# loochi-0_6.net
KiCad netlist of a schematic drawn in EAGLE
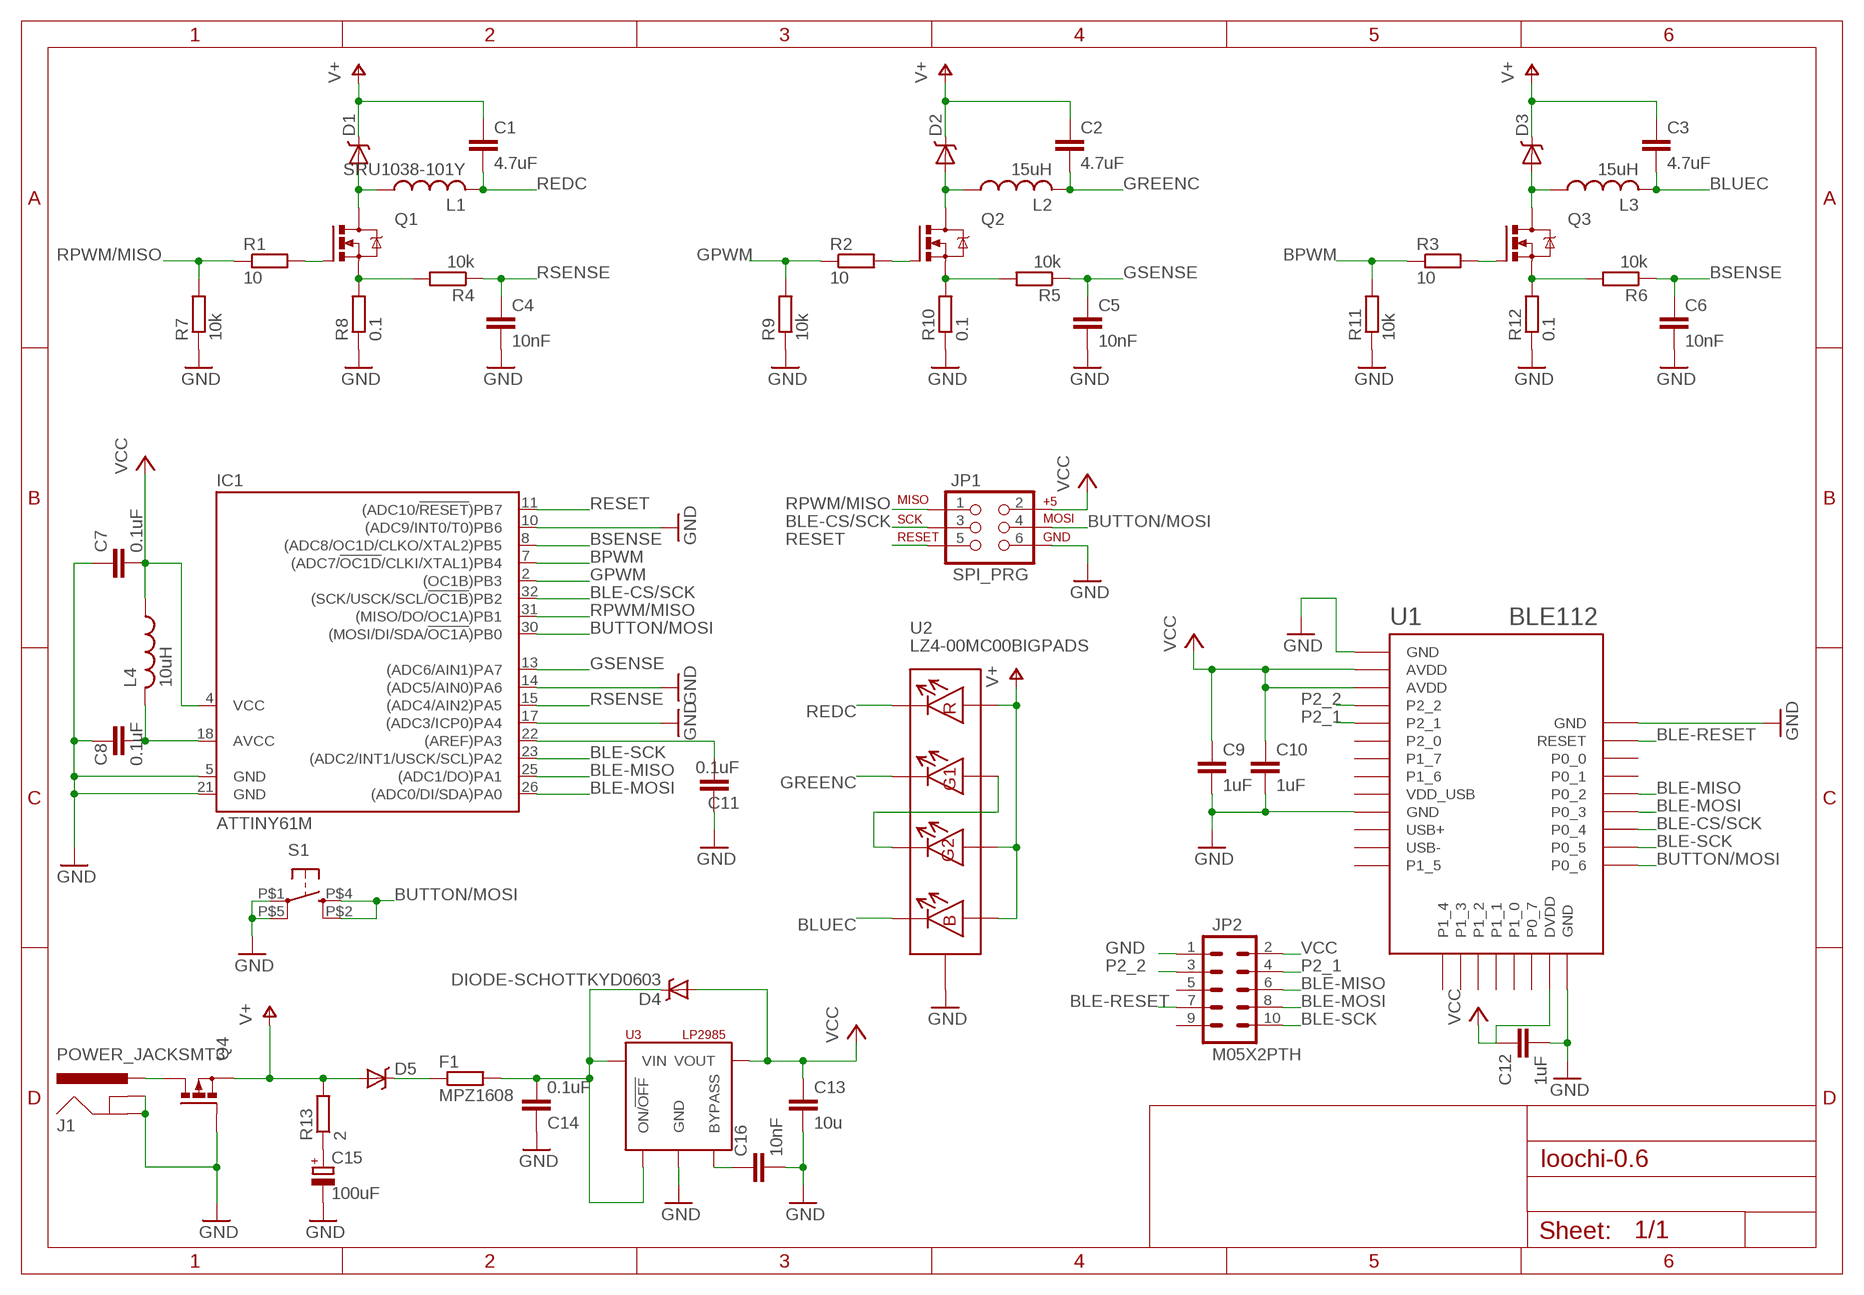
[diagram p0: schematic, sheet 1]

(export (version "E")
  (design (tool "Eeschema 10.0.6"))
  (components
    (comp (ref "C1")
      (value "4.7uF")
      (footprint "eagle-import:C0603")
      (libsource (lib "eagle-import") (part "C-EUC0603"))
    )
    (comp (ref "C2")
      (value "4.7uF")
      (footprint "eagle-import:C0603")
      (libsource (lib "eagle-import") (part "C-EUC0603"))
    )
    (comp (ref "C3")
      (value "4.7uF")
      (footprint "eagle-import:C0603")
      (libsource (lib "eagle-import") (part "C-EUC0603"))
    )
    (comp (ref "C4")
      (value "10nF")
      (footprint "eagle-import:C0603")
      (libsource (lib "eagle-import") (part "C-EUC0603"))
    )
    (comp (ref "C5")
      (value "10nF")
      (footprint "eagle-import:C0603")
      (libsource (lib "eagle-import") (part "C-EUC0603"))
    )
    (comp (ref "C6")
      (value "10nF")
      (footprint "eagle-import:C0603")
      (libsource (lib "eagle-import") (part "C-EUC0603"))
    )
    (comp (ref "C7")
      (value "0.1uF")
      (footprint "eagle-import:C0603")
      (libsource (lib "eagle-import") (part "C-EUC0603"))
    )
    (comp (ref "C8")
      (value "0.1uF")
      (footprint "eagle-import:C0603")
      (libsource (lib "eagle-import") (part "C-EUC0603"))
    )
    (comp (ref "C9")
      (value "1uF")
      (footprint "eagle-import:C0603")
      (libsource (lib "eagle-import") (part "C-EUC0603"))
    )
    (comp (ref "C10")
      (value "1uF")
      (footprint "eagle-import:C0603")
      (libsource (lib "eagle-import") (part "C-EUC0603"))
    )
    (comp (ref "C11")
      (value "0.1uF")
      (footprint "eagle-import:C0603")
      (libsource (lib "eagle-import") (part "C-EUC0603"))
    )
    (comp (ref "C12")
      (value "1uF")
      (footprint "eagle-import:C0603")
      (libsource (lib "eagle-import") (part "C-EUC0603"))
    )
    (comp (ref "C13")
      (value "10u")
      (footprint "eagle-import:C0603")
      (libsource (lib "eagle-import") (part "C-EUC0603"))
    )
    (comp (ref "C14")
      (value "0.1uF")
      (footprint "eagle-import:C0603K")
      (libsource (lib "eagle-import") (part "C-EUC0603K"))
    )
    (comp (ref "C15")
      (value "100uF")
      (footprint "eagle-import:PANASONIC_D")
      (libsource (lib "eagle-import") (part "CPOL-EUD"))
    )
    (comp (ref "C16")
      (value "10nF")
      (footprint "eagle-import:C0603")
      (libsource (lib "eagle-import") (part "C-EUC0603"))
    )
    (comp (ref "D1")
      (value "PMEG4010CEH")
      (footprint "eagle-import:SOD123F")
      (libsource (lib "eagle-import") (part "DIODE-SCHOTTKY"))
    )
    (comp (ref "D2")
      (value "PMEG4010CEH")
      (footprint "eagle-import:SOD123F")
      (libsource (lib "eagle-import") (part "DIODE-SCHOTTKY"))
    )
    (comp (ref "D3")
      (value "PMEG4010CEH")
      (footprint "eagle-import:SOD123F")
      (libsource (lib "eagle-import") (part "DIODE-SCHOTTKY"))
    )
    (comp (ref "D4")
      (value "DIODE-SCHOTTKYD0603")
      (footprint "eagle-import:D0603")
      (libsource (lib "eagle-import") (part "DIODE-SCHOTTKYD0603"))
    )
    (comp (ref "D5")
      (value "PMEG4010CEH")
      (footprint "eagle-import:SOD123F")
      (libsource (lib "eagle-import") (part "DIODE-SCHOTTKY"))
    )
    (comp (ref "F1")
      (value "MPZ1608")
      (footprint "eagle-import:R0603")
      (libsource (lib "eagle-import") (part "R-EU_R0603"))
    )
    (comp (ref "IC1")
      (value "ATTINY61M")
      (footprint "eagle-import:MLF32")
      (fields (field (name "OC_FARNELL") "unknown") (field (name "OC_NEWARK") "unknown"))
      (libsource (lib "eagle-import") (part "ATTINY61M"))
    )
    (comp (ref "J1")
      (value "POWER_JACKSMT3")
      (footprint "eagle-import:POWER-KYCONSMT3")
      (libsource (lib "eagle-import") (part "POWER_JACKSMT3"))
    )
    (comp (ref "JP1")
      (value "SPI_PRG")
      (footprint "eagle-import:2X3-NS")
      (libsource (lib "eagle-import") (part "AVR_SPI_PRG_6NS"))
    )
    (comp (ref "JP2")
      (value "M05X2PTH")
      (footprint "eagle-import:AVR_ICSP")
      (libsource (lib "eagle-import") (part "M05X2PTH"))
    )
    (comp (ref "L1")
      (value "SRU1038-101Y")
      (footprint "eagle-import:BOURNS-SRU1038")
      (libsource (lib "eagle-import") (part "L-USBOURNS-SRU1038"))
    )
    (comp (ref "L2")
      (value "15uH")
      (footprint "eagle-import:BOURNS-SRU1038")
      (libsource (lib "eagle-import") (part "L-USBOURNS-SRU1038"))
    )
    (comp (ref "L3")
      (value "15uH")
      (footprint "eagle-import:BOURNS-SRU1038")
      (libsource (lib "eagle-import") (part "L-USBOURNS-SRU1038"))
    )
    (comp (ref "L4")
      (value "10uH")
      (footprint "eagle-import:L0603")
      (libsource (lib "eagle-import") (part "L-USL0603"))
    )
    (comp (ref "Q1")
      (value "PMN25ENSOT457")
      (footprint "eagle-import:SOT457")
      (libsource (lib "eagle-import") (part "PMN25ENSOT457"))
    )
    (comp (ref "Q2")
      (value "PMN25ENSOT457")
      (footprint "eagle-import:SOT457")
      (libsource (lib "eagle-import") (part "PMN25ENSOT457"))
    )
    (comp (ref "Q3")
      (value "PMN25ENSOT457")
      (footprint "eagle-import:SOT457")
      (libsource (lib "eagle-import") (part "PMN25ENSOT457"))
    )
    (comp (ref "Q4")
      (value "FDC654P")
      (footprint "eagle-import:SUPERSOT6")
      (libsource (lib "eagle-import") (part "FDC654P"))
    )
    (comp (ref "R1")
      (value "10")
      (footprint "eagle-import:R0603")
      (libsource (lib "eagle-import") (part "R-EU_R0603"))
    )
    (comp (ref "R2")
      (value "10")
      (footprint "eagle-import:R0603")
      (libsource (lib "eagle-import") (part "R-EU_R0603"))
    )
    (comp (ref "R3")
      (value "10")
      (footprint "eagle-import:R0603")
      (libsource (lib "eagle-import") (part "R-EU_R0603"))
    )
    (comp (ref "R4")
      (value "10k")
      (footprint "eagle-import:R0603")
      (libsource (lib "eagle-import") (part "R-EU_R0603"))
    )
    (comp (ref "R5")
      (value "10k")
      (footprint "eagle-import:R0603")
      (libsource (lib "eagle-import") (part "R-EU_R0603"))
    )
    (comp (ref "R6")
      (value "10k")
      (footprint "eagle-import:R0603")
      (libsource (lib "eagle-import") (part "R-EU_R0603"))
    )
    (comp (ref "R7")
      (value "10k")
      (footprint "eagle-import:R0603")
      (libsource (lib "eagle-import") (part "R-EU_R0603"))
    )
    (comp (ref "R8")
      (value "0.1")
      (footprint "eagle-import:R0603")
      (libsource (lib "eagle-import") (part "R-EU_R0603"))
    )
    (comp (ref "R9")
      (value "10k")
      (footprint "eagle-import:R0603")
      (libsource (lib "eagle-import") (part "R-EU_R0603"))
    )
    (comp (ref "R10")
      (value "0.1")
      (footprint "eagle-import:R0603")
      (libsource (lib "eagle-import") (part "R-EU_R0603"))
    )
    (comp (ref "R11")
      (value "10k")
      (footprint "eagle-import:R0603")
      (libsource (lib "eagle-import") (part "R-EU_R0603"))
    )
    (comp (ref "R12")
      (value "0.1")
      (footprint "eagle-import:R0603")
      (libsource (lib "eagle-import") (part "R-EU_R0603"))
    )
    (comp (ref "R13")
      (value "2")
      (footprint "eagle-import:R0603")
      (libsource (lib "eagle-import") (part "R-EU_R0603"))
    )
    (comp (ref "S1")
      (value "TAC_SWITCH")
      (footprint "eagle-import:CK-KMS_PEGS")
      (libsource (lib "eagle-import") (part "TAC_SWITCH"))
    )
    (comp (ref "U1")
      (value "BLE112")
      (footprint "eagle-import:SF-BLUEGIGA_BLE112-A")
      (libsource (lib "eagle-import") (part "SF-BLUEGIGA_BLE112-A-VISUAL"))
    )
    (comp (ref "U2")
      (value "LZ4-00MC00BIGPADS")
      (footprint "eagle-import:LZ4-00MC00-BIGPADS")
      (libsource (lib "eagle-import") (part "LZ4-00MC00BIGPADS"))
    )
    (comp (ref "U3")
      (value "LP2985")
      (footprint "eagle-import:DBV")
      (libsource (lib "eagle-import") (part "LP2985"))
    )
  )
  (nets
    (net (code "1") (name "/BLE-CS{slash}SCK") (class "Default")
      (node (ref "IC1") (pin "32") (pinfunction "(SCK/USCK/SCL/~{OC1B})PB2_32") (pintype "bidirectional"))
      (node (ref "JP1") (pin "3") (pinfunction "3_3") (pintype "passive"))
      (node (ref "U1") (pin "P0_4") (pinfunction "P0_4_P0_4") (pintype "bidirectional"))
    )
    (net (code "2") (name "/BLE-MISO") (class "Default")
      (node (ref "IC1") (pin "25") (pinfunction "(ADC1/DO)PA1_25") (pintype "bidirectional"))
      (node (ref "JP2") (pin "6") (pinfunction "6_6") (pintype "passive"))
      (node (ref "U1") (pin "P0_2") (pinfunction "P0_2_P0_2") (pintype "bidirectional"))
    )
    (net (code "3") (name "/BLE-MOSI") (class "Default")
      (node (ref "IC1") (pin "26") (pinfunction "(ADC0/DI/SDA)PA0_26") (pintype "bidirectional"))
      (node (ref "JP2") (pin "8") (pinfunction "8_8") (pintype "passive"))
      (node (ref "U1") (pin "P0_3") (pinfunction "P0_3_P0_3") (pintype "bidirectional"))
    )
    (net (code "4") (name "/BLE-RESET") (class "Default")
      (node (ref "JP2") (pin "7") (pinfunction "7_7") (pintype "passive"))
      (node (ref "U1") (pin "RESET") (pinfunction "RESET_RESET") (pintype "input"))
    )
    (net (code "5") (name "/BLE-SCK") (class "Default")
      (node (ref "IC1") (pin "23") (pinfunction "(ADC2/INT1/USCK/SCL)PA2_23") (pintype "bidirectional"))
      (node (ref "JP2") (pin "10") (pinfunction "10_10") (pintype "passive"))
      (node (ref "U1") (pin "P0_5") (pinfunction "P0_5_P0_5") (pintype "bidirectional"))
    )
    (net (code "6") (name "/BLUEC") (class "Default")
      (node (ref "C3") (pin "2") (pinfunction "2_2") (pintype "passive"))
      (node (ref "L3") (pin "P$2") (pinfunction "2_P$2") (pintype "passive"))
      (node (ref "U2") (pin "P$8") (pinfunction "P$8_P$8") (pintype "bidirectional"))
    )
    (net (code "7") (name "/BPWM") (class "Default")
      (node (ref "IC1") (pin "7") (pinfunction "(ADC7/~{OC1D}/CLKI/XTAL1)PB4_7") (pintype "bidirectional"))
      (node (ref "R11") (pin "2") (pinfunction "2_2") (pintype "passive"))
      (node (ref "R3") (pin "1") (pinfunction "1_1") (pintype "passive"))
    )
    (net (code "8") (name "/BSENSE") (class "Default")
      (node (ref "C6") (pin "1") (pinfunction "1_1") (pintype "passive"))
      (node (ref "IC1") (pin "8") (pinfunction "(ADC8/OC1D/CLKO/XTAL2)PB5_8") (pintype "bidirectional"))
      (node (ref "R6") (pin "1") (pinfunction "1_1") (pintype "passive"))
    )
    (net (code "9") (name "/BUTTON{slash}MOSI") (class "Default")
      (node (ref "IC1") (pin "30") (pinfunction "(MOSI/DI/SDA/~{OC1A})PB0_30") (pintype "bidirectional"))
      (node (ref "JP1") (pin "4") (pinfunction "4_4") (pintype "passive"))
      (node (ref "S1") (pin "P$2") (pinfunction "4_P$2") (pintype "passive"))
      (node (ref "S1") (pin "P$4") (pinfunction "3_P$4") (pintype "passive"))
      (node (ref "U1") (pin "P0_6") (pinfunction "P0_6_P0_6") (pintype "bidirectional"))
    )
    (net (code "10") (name "/GPWM") (class "Default")
      (node (ref "IC1") (pin "2") (pinfunction "(OC1B)PB3_2") (pintype "bidirectional"))
      (node (ref "R2") (pin "1") (pinfunction "1_1") (pintype "passive"))
      (node (ref "R9") (pin "2") (pinfunction "2_2") (pintype "passive"))
    )
    (net (code "11") (name "/GREENC") (class "Default")
      (node (ref "C2") (pin "2") (pinfunction "2_2") (pintype "passive"))
      (node (ref "L2") (pin "P$2") (pinfunction "2_P$2") (pintype "passive"))
      (node (ref "U2") (pin "P$6") (pinfunction "P$6_P$6") (pintype "bidirectional"))
    )
    (net (code "12") (name "/GSENSE") (class "Default")
      (node (ref "C5") (pin "1") (pinfunction "1_1") (pintype "passive"))
      (node (ref "IC1") (pin "13") (pinfunction "(ADC6/AIN1)PA7_13") (pintype "bidirectional"))
      (node (ref "R5") (pin "1") (pinfunction "1_1") (pintype "passive"))
    )
    (net (code "13") (name "/P2_1") (class "Default")
      (node (ref "JP2") (pin "4") (pinfunction "4_4") (pintype "passive"))
      (node (ref "U1") (pin "P2_1") (pinfunction "P2_1_P2_1") (pintype "bidirectional"))
    )
    (net (code "14") (name "/P2_2") (class "Default")
      (node (ref "JP2") (pin "3") (pinfunction "3_3") (pintype "passive"))
      (node (ref "U1") (pin "P2_2") (pinfunction "P2_2_P2_2") (pintype "bidirectional"))
    )
    (net (code "15") (name "/REDC") (class "Default")
      (node (ref "C1") (pin "2") (pinfunction "2_2") (pintype "passive"))
      (node (ref "L1") (pin "P$2") (pinfunction "2_P$2") (pintype "passive"))
      (node (ref "U2") (pin "P$4") (pinfunction "P$4_P$4") (pintype "bidirectional"))
    )
    (net (code "16") (name "/RESET") (class "Default")
      (node (ref "IC1") (pin "11") (pinfunction "(ADC10/~{RESET})PB7_11") (pintype "bidirectional"))
      (node (ref "JP1") (pin "5") (pinfunction "5_5") (pintype "passive"))
    )
    (net (code "17") (name "/RPWM{slash}MISO") (class "Default")
      (node (ref "IC1") (pin "31") (pinfunction "(MISO/DO/OC1A)PB1_31") (pintype "bidirectional"))
      (node (ref "JP1") (pin "1") (pinfunction "1_1") (pintype "passive"))
      (node (ref "R1") (pin "1") (pinfunction "1_1") (pintype "passive"))
      (node (ref "R7") (pin "2") (pinfunction "2_2") (pintype "passive"))
    )
    (net (code "18") (name "/RSENSE") (class "Default")
      (node (ref "C4") (pin "1") (pinfunction "1_1") (pintype "passive"))
      (node (ref "IC1") (pin "15") (pinfunction "(ADC4/AIN2)PA5_15") (pintype "bidirectional"))
      (node (ref "R4") (pin "1") (pinfunction "1_1") (pintype "passive"))
    )
    (net (code "19") (name "/VDD_USB") (class "Default")
      (node (ref "U1") (pin "VDD_USB") (pinfunction "VDD_USB_VDD_USB") (pintype "power_in"))
    )
    (net (code "20") (name "GND") (class "Default")
      (node (ref "C10") (pin "2") (pinfunction "2_2") (pintype "passive"))
      (node (ref "C11") (pin "1") (pinfunction "1_1") (pintype "passive"))
      (node (ref "C12") (pin "2") (pinfunction "2_2") (pintype "passive"))
      (node (ref "C13") (pin "2") (pinfunction "2_2") (pintype "passive"))
      (node (ref "C14") (pin "1") (pinfunction "1_1") (pintype "passive"))
      (node (ref "C15") (pin "-") (pinfunction "-_-") (pintype "passive"))
      (node (ref "C16") (pin "2") (pinfunction "2_2") (pintype "passive"))
      (node (ref "C4") (pin "2") (pinfunction "2_2") (pintype "passive"))
      (node (ref "C5") (pin "2") (pinfunction "2_2") (pintype "passive"))
      (node (ref "C6") (pin "2") (pinfunction "2_2") (pintype "passive"))
      (node (ref "C7") (pin "1") (pinfunction "1_1") (pintype "passive"))
      (node (ref "C8") (pin "1") (pinfunction "1_1") (pintype "passive"))
      (node (ref "C9") (pin "2") (pinfunction "2_2") (pintype "passive"))
      (node (ref "IC1") (pin "10") (pinfunction "(ADC9/INT0/T0)PB6_10") (pintype "bidirectional"))
      (node (ref "IC1") (pin "14") (pinfunction "(ADC5/AIN0)PA6_14") (pintype "bidirectional"))
      (node (ref "IC1") (pin "17") (pinfunction "(ADC3/ICP0)PA4_17") (pintype "bidirectional"))
      (node (ref "IC1") (pin "21") (pinfunction "GND_21") (pintype "power_in"))
      (node (ref "IC1") (pin "5") (pinfunction "GND_5") (pintype "power_in"))
      (node (ref "J1") (pin "P$2") (pinfunction "GND_P$2") (pintype "bidirectional"))
      (node (ref "J1") (pin "P$3") (pinfunction "GNDBREAK_P$3") (pintype "bidirectional"))
      (node (ref "JP1") (pin "6") (pinfunction "6_6") (pintype "passive"))
      (node (ref "JP2") (pin "1") (pinfunction "1_1") (pintype "passive"))
      (node (ref "Q4") (pin "P$3") (pinfunction "G_P$3") (pintype "passive"))
      (node (ref "R10") (pin "1") (pinfunction "1_1") (pintype "passive"))
      (node (ref "R11") (pin "1") (pinfunction "1_1") (pintype "passive"))
      (node (ref "R12") (pin "1") (pinfunction "1_1") (pintype "passive"))
      (node (ref "R7") (pin "1") (pinfunction "1_1") (pintype "passive"))
      (node (ref "R8") (pin "1") (pinfunction "1_1") (pintype "passive"))
      (node (ref "R9") (pin "1") (pinfunction "1_1") (pintype "passive"))
      (node (ref "S1") (pin "P$1") (pinfunction "1_P$1") (pintype "passive"))
      (node (ref "S1") (pin "P$5") (pinfunction "2_P$5") (pintype "passive"))
      (node (ref "U1") (pin "GND1") (pinfunction "GND_GND1") (pintype "power_in"))
      (node (ref "U1") (pin "GND2") (pinfunction "GND_GND2") (pintype "power_in"))
      (node (ref "U1") (pin "GND3") (pinfunction "GND_GND3") (pintype "power_in"))
      (node (ref "U1") (pin "GND4") (pinfunction "GND_GND4") (pintype "power_in"))
      (node (ref "U2") (pin "P$9") (pinfunction "THERMAL_P$9") (pintype "bidirectional"))
      (node (ref "U2") (pin "THERMAL") (pinfunction "THERMAL_THERMAL") (pintype "bidirectional"))
      (node (ref "U2") (pin "THERMAL1") (pinfunction "THERMAL_THERMAL1") (pintype "bidirectional"))
      (node (ref "U2") (pin "THERMAL2") (pinfunction "THERMAL_THERMAL2") (pintype "bidirectional"))
      (node (ref "U2") (pin "THERMAL3") (pinfunction "THERMAL_THERMAL3") (pintype "bidirectional"))
      (node (ref "U2") (pin "THERMAL4") (pinfunction "THERMAL_THERMAL4") (pintype "bidirectional"))
      (node (ref "U2") (pin "THERMAL5") (pinfunction "THERMAL_THERMAL5") (pintype "bidirectional"))
      (node (ref "U2") (pin "THERMAL6") (pinfunction "THERMAL_THERMAL6") (pintype "bidirectional"))
      (node (ref "U2") (pin "THERMAL7") (pinfunction "THERMAL_THERMAL7") (pintype "bidirectional"))
      (node (ref "U2") (pin "THERMAL8") (pinfunction "THERMAL_THERMAL8") (pintype "bidirectional"))
      (node (ref "U2") (pin "THERMAL9") (pinfunction "THERMAL_THERMAL9") (pintype "bidirectional"))
      (node (ref "U3") (pin "2") (pinfunction "GND_2") (pintype "power_in"))
    )
    (net (code "21") (name "Net-(C15-Pad+)") (class "Default")
      (node (ref "C15") (pin "+") (pinfunction "+_+") (pintype "passive"))
      (node (ref "R13") (pin "1") (pinfunction "1_1") (pintype "passive"))
    )
    (net (code "22") (name "Net-(D1-A)") (class "Default")
      (node (ref "D1") (pin "P$A") (pinfunction "A_P$A") (pintype "passive"))
      (node (ref "L1") (pin "P$1") (pinfunction "1_P$1") (pintype "passive"))
      (node (ref "Q1") (pin "P$1") (pinfunction "D_P$1") (pintype "passive"))
      (node (ref "Q1") (pin "P$2") (pinfunction "D_P$2") (pintype "passive"))
      (node (ref "Q1") (pin "P$5") (pinfunction "D_P$5") (pintype "passive"))
      (node (ref "Q1") (pin "P$6") (pinfunction "D_P$6") (pintype "passive"))
    )
    (net (code "23") (name "Net-(D2-A)") (class "Default")
      (node (ref "D2") (pin "P$A") (pinfunction "A_P$A") (pintype "passive"))
      (node (ref "L2") (pin "P$1") (pinfunction "1_P$1") (pintype "passive"))
      (node (ref "Q2") (pin "P$1") (pinfunction "D_P$1") (pintype "passive"))
      (node (ref "Q2") (pin "P$2") (pinfunction "D_P$2") (pintype "passive"))
      (node (ref "Q2") (pin "P$5") (pinfunction "D_P$5") (pintype "passive"))
      (node (ref "Q2") (pin "P$6") (pinfunction "D_P$6") (pintype "passive"))
    )
    (net (code "24") (name "Net-(D3-A)") (class "Default")
      (node (ref "D3") (pin "P$A") (pinfunction "A_P$A") (pintype "passive"))
      (node (ref "L3") (pin "P$1") (pinfunction "1_P$1") (pintype "passive"))
      (node (ref "Q3") (pin "P$1") (pinfunction "D_P$1") (pintype "passive"))
      (node (ref "Q3") (pin "P$2") (pinfunction "D_P$2") (pintype "passive"))
      (node (ref "Q3") (pin "P$5") (pinfunction "D_P$5") (pintype "passive"))
      (node (ref "Q3") (pin "P$6") (pinfunction "D_P$6") (pintype "passive"))
    )
    (net (code "25") (name "Net-(D4-C)") (class "Default")
      (node (ref "C14") (pin "2") (pinfunction "2_2") (pintype "passive"))
      (node (ref "D4") (pin "CATHODE") (pinfunction "C_CATHODE") (pintype "passive"))
      (node (ref "F1") (pin "2") (pinfunction "2_2") (pintype "passive"))
      (node (ref "U3") (pin "1") (pinfunction "VIN_1") (pintype "power_in"))
      (node (ref "U3") (pin "3") (pinfunction "ON/~{OFF}_3") (pintype "bidirectional"))
    )
    (net (code "26") (name "Net-(D5-C)") (class "Default")
      (node (ref "D5") (pin "P$C") (pinfunction "C_P$C") (pintype "passive"))
      (node (ref "F1") (pin "1") (pinfunction "1_1") (pintype "passive"))
    )
    (net (code "27") (name "Net-(IC1-(AREF)PA3)") (class "Default")
      (node (ref "C11") (pin "2") (pinfunction "2_2") (pintype "passive"))
      (node (ref "IC1") (pin "22") (pinfunction "(AREF)PA3_22") (pintype "bidirectional"))
    )
    (net (code "28") (name "Net-(IC1-AVCC)") (class "Default")
      (node (ref "C8") (pin "2") (pinfunction "2_2") (pintype "passive"))
      (node (ref "IC1") (pin "18") (pinfunction "AVCC_18") (pintype "power_in"))
      (node (ref "L4") (pin "2") (pinfunction "2_2") (pintype "passive"))
    )
    (net (code "29") (name "Net-(J1-PWR)") (class "Default")
      (node (ref "J1") (pin "P$1") (pinfunction "PWR_P$1") (pintype "bidirectional"))
      (node (ref "Q4") (pin "P$1") (pinfunction "D_P$1") (pintype "passive"))
      (node (ref "Q4") (pin "P$2") (pinfunction "D_P$2") (pintype "passive"))
      (node (ref "Q4") (pin "P$5") (pinfunction "D_P$5") (pintype "passive"))
      (node (ref "Q4") (pin "P$6") (pinfunction "D_P$6") (pintype "passive"))
    )
    (net (code "30") (name "Net-(Q1-G)") (class "Default")
      (node (ref "Q1") (pin "P$3") (pinfunction "G_P$3") (pintype "passive"))
      (node (ref "R1") (pin "2") (pinfunction "2_2") (pintype "passive"))
    )
    (net (code "31") (name "Net-(Q1-S)") (class "Default")
      (node (ref "Q1") (pin "P$4") (pinfunction "S_P$4") (pintype "passive"))
      (node (ref "R4") (pin "2") (pinfunction "2_2") (pintype "passive"))
      (node (ref "R8") (pin "2") (pinfunction "2_2") (pintype "passive"))
    )
    (net (code "32") (name "Net-(Q2-G)") (class "Default")
      (node (ref "Q2") (pin "P$3") (pinfunction "G_P$3") (pintype "passive"))
      (node (ref "R2") (pin "2") (pinfunction "2_2") (pintype "passive"))
    )
    (net (code "33") (name "Net-(Q2-S)") (class "Default")
      (node (ref "Q2") (pin "P$4") (pinfunction "S_P$4") (pintype "passive"))
      (node (ref "R10") (pin "2") (pinfunction "2_2") (pintype "passive"))
      (node (ref "R5") (pin "2") (pinfunction "2_2") (pintype "passive"))
    )
    (net (code "34") (name "Net-(Q3-G)") (class "Default")
      (node (ref "Q3") (pin "P$3") (pinfunction "G_P$3") (pintype "passive"))
      (node (ref "R3") (pin "2") (pinfunction "2_2") (pintype "passive"))
    )
    (net (code "35") (name "Net-(Q3-S)") (class "Default")
      (node (ref "Q3") (pin "P$4") (pinfunction "S_P$4") (pintype "passive"))
      (node (ref "R12") (pin "2") (pinfunction "2_2") (pintype "passive"))
      (node (ref "R6") (pin "2") (pinfunction "2_2") (pintype "passive"))
    )
    (net (code "36") (name "Net-(U2-PadP$2)") (class "Default")
      (node (ref "U2") (pin "P$2") (pinfunction "P$2_P$2") (pintype "bidirectional"))
      (node (ref "U2") (pin "P$5") (pinfunction "P$5_P$5") (pintype "bidirectional"))
    )
    (net (code "37") (name "Net-(U3-BYPASS)") (class "Default")
      (node (ref "C16") (pin "1") (pinfunction "1_1") (pintype "passive"))
      (node (ref "U3") (pin "4") (pinfunction "BYPASS_4") (pintype "bidirectional"))
    )
    (net (code "38") (name "V+") (class "Default")
      (node (ref "C1") (pin "1") (pinfunction "1_1") (pintype "passive"))
      (node (ref "C2") (pin "1") (pinfunction "1_1") (pintype "passive"))
      (node (ref "C3") (pin "1") (pinfunction "1_1") (pintype "passive"))
      (node (ref "D1") (pin "P$C") (pinfunction "C_P$C") (pintype "passive"))
      (node (ref "D2") (pin "P$C") (pinfunction "C_P$C") (pintype "passive"))
      (node (ref "D3") (pin "P$C") (pinfunction "C_P$C") (pintype "passive"))
      (node (ref "D5") (pin "P$A") (pinfunction "A_P$A") (pintype "passive"))
      (node (ref "Q4") (pin "P$4") (pinfunction "S_P$4") (pintype "passive"))
      (node (ref "R13") (pin "2") (pinfunction "2_2") (pintype "passive"))
      (node (ref "U2") (pin "P$1") (pinfunction "P$1_P$1") (pintype "bidirectional"))
      (node (ref "U2") (pin "P$3") (pinfunction "P$3_P$3") (pintype "bidirectional"))
      (node (ref "U2") (pin "P$7") (pinfunction "P$7_P$7") (pintype "bidirectional"))
    )
    (net (code "39") (name "VCC") (class "Default")
      (node (ref "C10") (pin "1") (pinfunction "1_1") (pintype "passive"))
      (node (ref "C12") (pin "1") (pinfunction "1_1") (pintype "passive"))
      (node (ref "C13") (pin "1") (pinfunction "1_1") (pintype "passive"))
      (node (ref "C7") (pin "2") (pinfunction "2_2") (pintype "passive"))
      (node (ref "C9") (pin "1") (pinfunction "1_1") (pintype "passive"))
      (node (ref "D4") (pin "ANODE") (pinfunction "A_ANODE") (pintype "passive"))
      (node (ref "IC1") (pin "4") (pinfunction "VCC_4") (pintype "power_in"))
      (node (ref "JP1") (pin "2") (pinfunction "2_2") (pintype "passive"))
      (node (ref "JP2") (pin "2") (pinfunction "2_2") (pintype "passive"))
      (node (ref "L4") (pin "1") (pinfunction "1_1") (pintype "passive"))
      (node (ref "U1") (pin "AVDD1") (pinfunction "AVDD_AVDD1") (pintype "power_in"))
      (node (ref "U1") (pin "AVDD2") (pinfunction "AVDD_AVDD2") (pintype "power_in"))
      (node (ref "U1") (pin "DVDD") (pinfunction "DVDD_DVDD") (pintype "power_in"))
      (node (ref "U3") (pin "5") (pinfunction "VOUT_5") (pintype "bidirectional"))
    )
    (net (code "40") (name "unconnected-(JP2-Pad5)") (class "Default")
      (node (ref "JP2") (pin "5") (pinfunction "5_5") (pintype "passive"))
    )
    (net (code "41") (name "unconnected-(JP2-Pad9)") (class "Default")
      (node (ref "JP2") (pin "9") (pinfunction "9_9") (pintype "passive"))
    )
    (net (code "42") (name "unconnected-(U1-PadP0_0)") (class "Default")
      (node (ref "U1") (pin "P0_0") (pinfunction "P0_0_P0_0") (pintype "bidirectional"))
    )
    (net (code "43") (name "unconnected-(U1-PadP0_1)") (class "Default")
      (node (ref "U1") (pin "P0_1") (pinfunction "P0_1_P0_1") (pintype "bidirectional"))
    )
    (net (code "44") (name "unconnected-(U1-PadP0_7)") (class "Default")
      (node (ref "U1") (pin "P0_7") (pinfunction "P0_7_P0_7") (pintype "bidirectional"))
    )
    (net (code "45") (name "unconnected-(U1-PadP1_0)") (class "Default")
      (node (ref "U1") (pin "P1_0") (pinfunction "P1_0_P1_0") (pintype "bidirectional"))
    )
    (net (code "46") (name "unconnected-(U1-PadP1_1)") (class "Default")
      (node (ref "U1") (pin "P1_1") (pinfunction "P1_1_P1_1") (pintype "bidirectional"))
    )
    (net (code "47") (name "unconnected-(U1-PadP1_2)") (class "Default")
      (node (ref "U1") (pin "P1_2") (pinfunction "P1_2_P1_2") (pintype "bidirectional"))
    )
    (net (code "48") (name "unconnected-(U1-PadP1_3)") (class "Default")
      (node (ref "U1") (pin "P1_3") (pinfunction "P1_3_P1_3") (pintype "bidirectional"))
    )
    (net (code "49") (name "unconnected-(U1-PadP1_4)") (class "Default")
      (node (ref "U1") (pin "P1_4") (pinfunction "P1_4_P1_4") (pintype "bidirectional"))
    )
    (net (code "50") (name "unconnected-(U1-PadP1_5)") (class "Default")
      (node (ref "U1") (pin "P1_5") (pinfunction "P1_5_P1_5") (pintype "bidirectional"))
    )
    (net (code "51") (name "unconnected-(U1-PadP1_6)") (class "Default")
      (node (ref "U1") (pin "P1_6") (pinfunction "P1_6_P1_6") (pintype "bidirectional"))
    )
    (net (code "52") (name "unconnected-(U1-PadP1_7)") (class "Default")
      (node (ref "U1") (pin "P1_7") (pinfunction "P1_7_P1_7") (pintype "bidirectional"))
    )
    (net (code "53") (name "unconnected-(U1-PadP2_0)") (class "Default")
      (node (ref "U1") (pin "P2_0") (pinfunction "P2_0_P2_0") (pintype "bidirectional"))
    )
    (net (code "54") (name "unconnected-(U1-PadUSB+)") (class "Default")
      (node (ref "U1") (pin "USB+") (pinfunction "USB+_USB+") (pintype "bidirectional"))
    )
    (net (code "55") (name "unconnected-(U1-PadUSB-)") (class "Default")
      (node (ref "U1") (pin "USB-") (pinfunction "USB-_USB-") (pintype "bidirectional"))
    )
  )
)
